# generic_victim.net
KiCad netlist of a schematic drawn in EAGLE
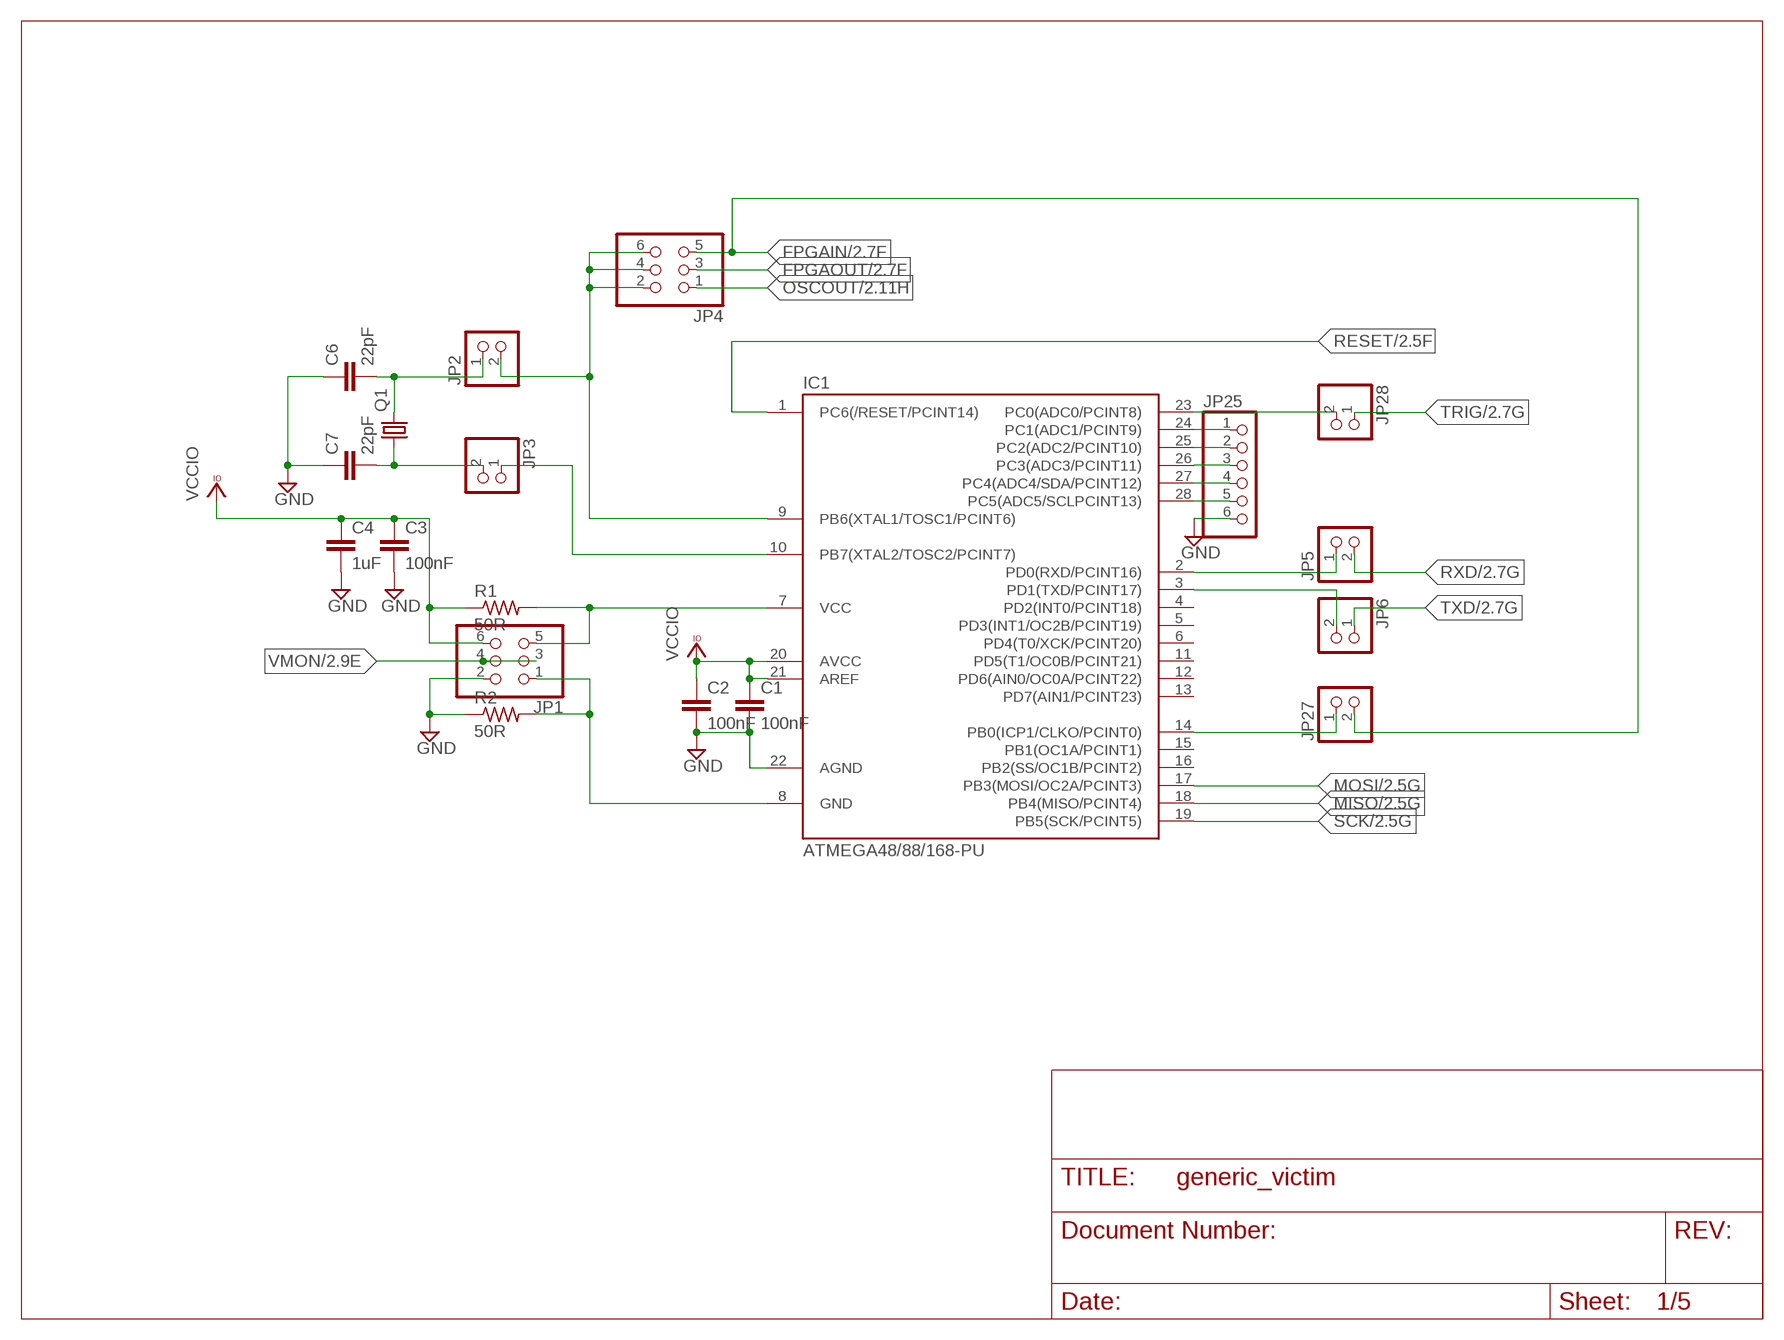
[diagram p0: schematic, sheet 1]
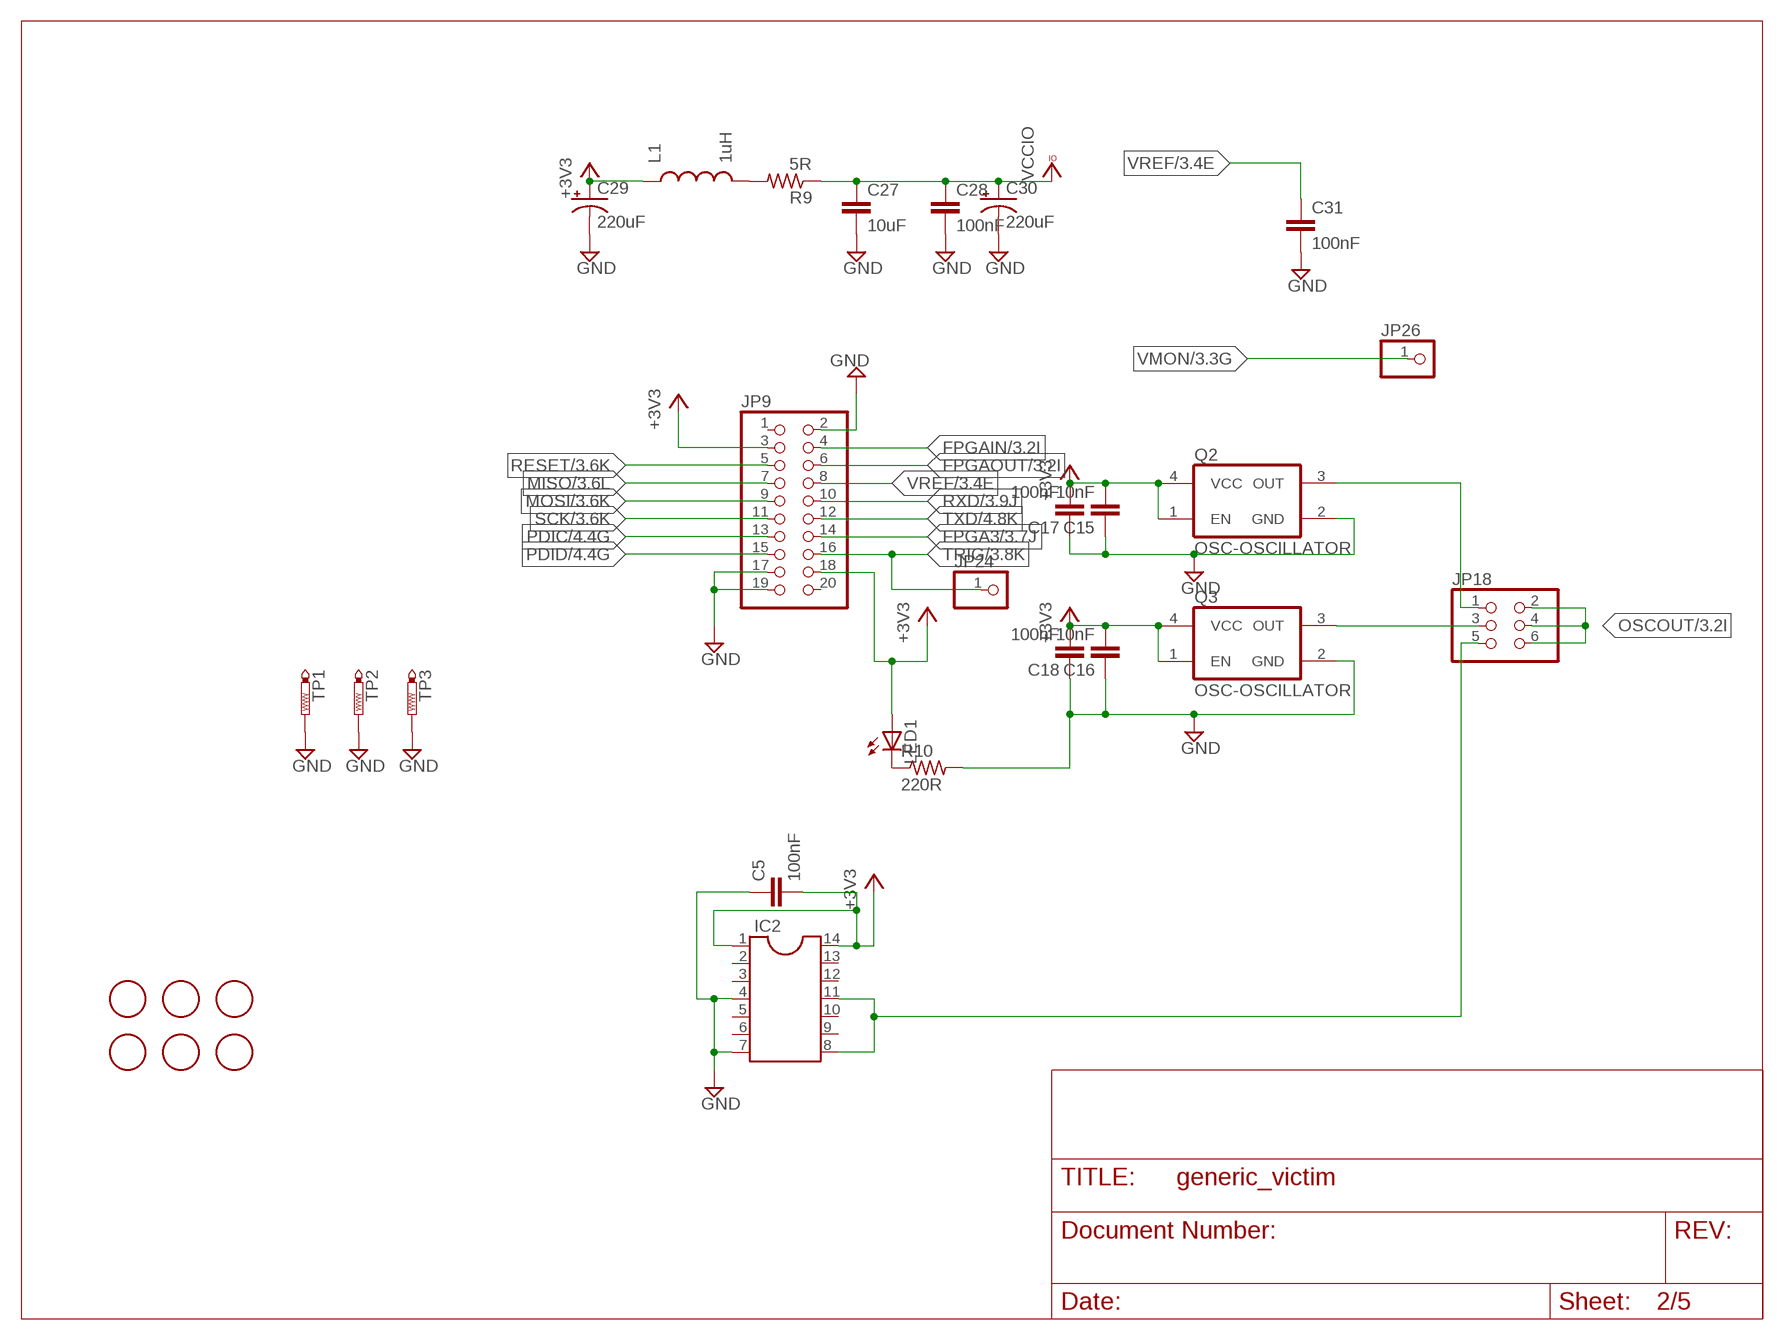
[diagram p1: schematic, sheet 2]
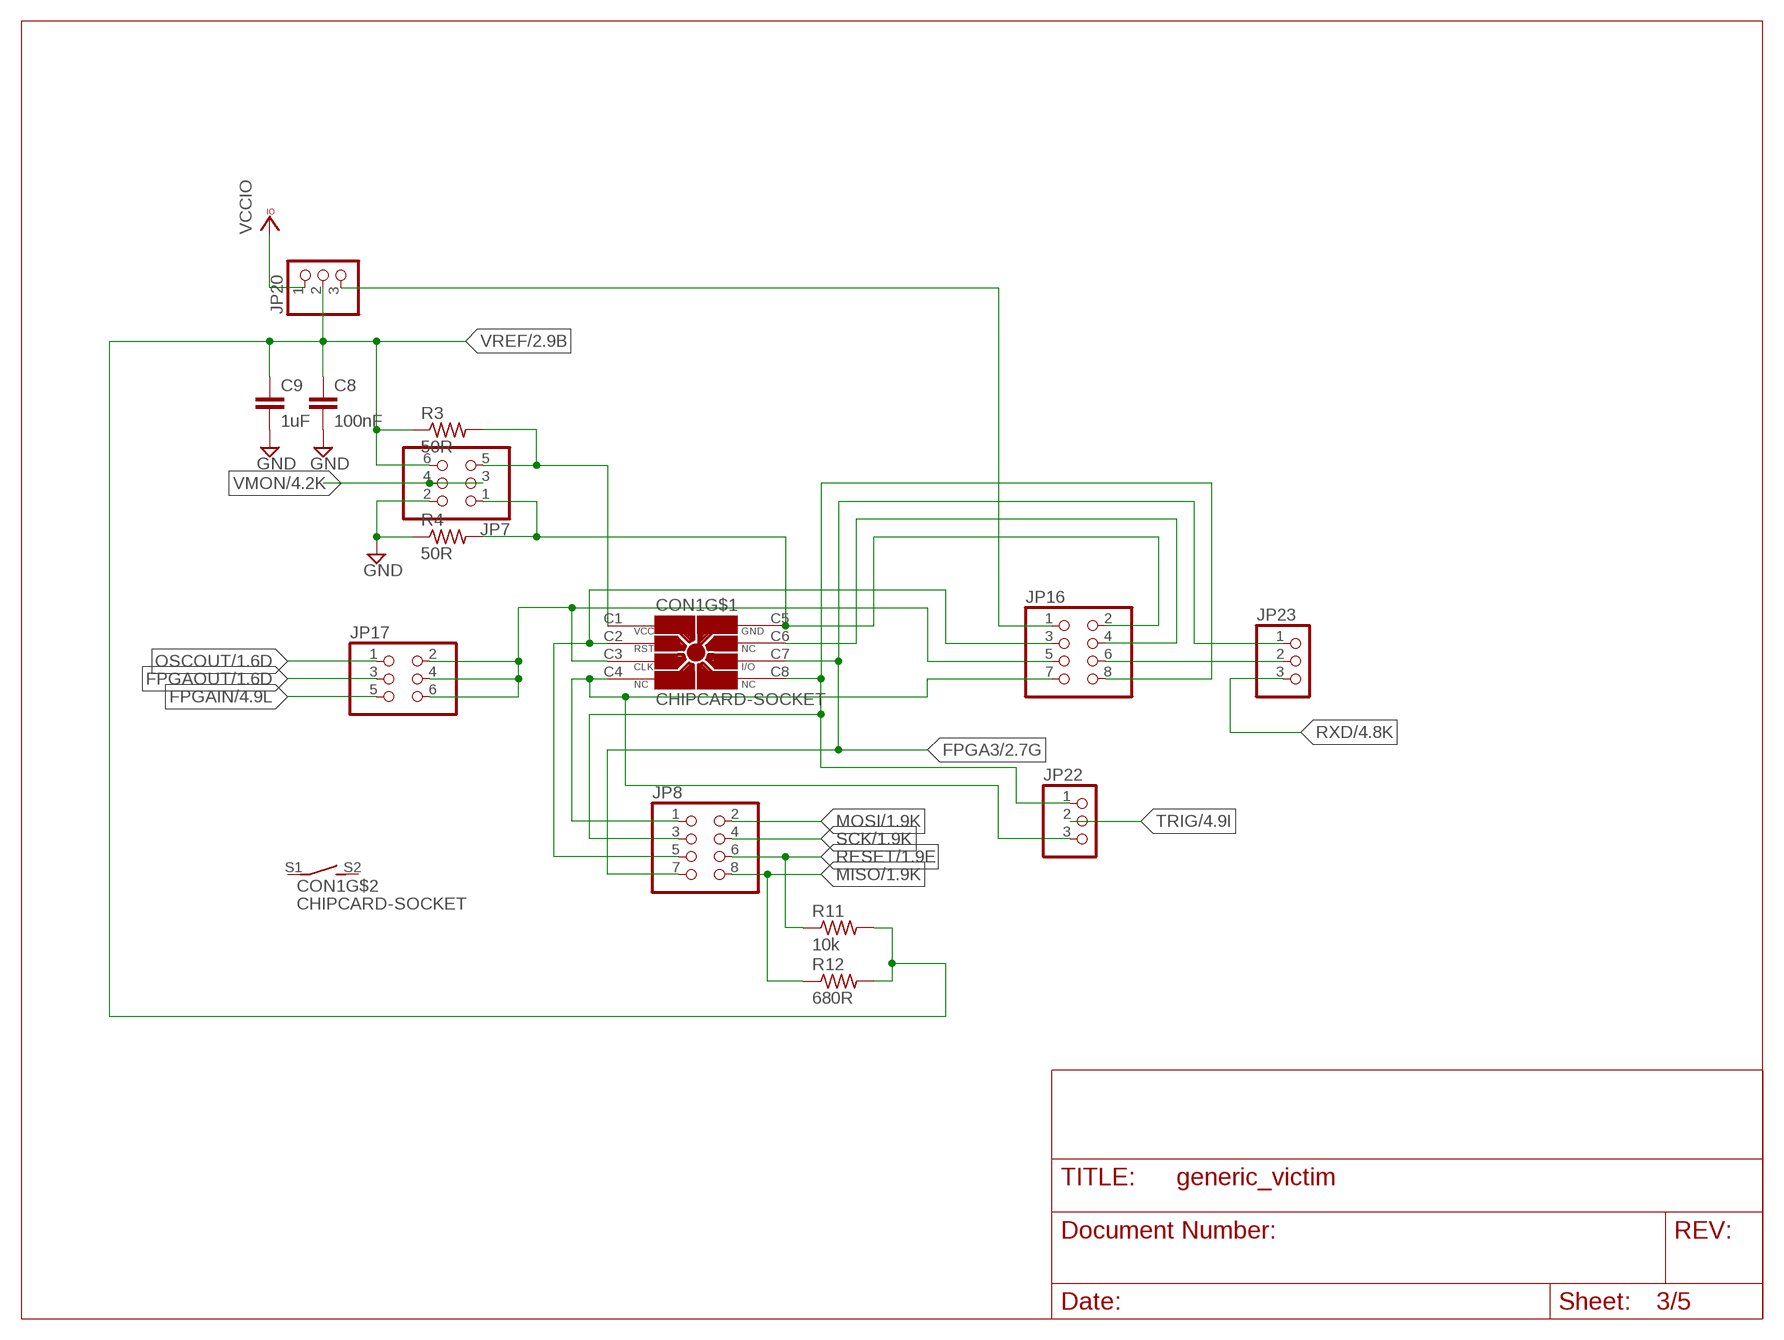
[diagram p2: schematic, sheet 3]
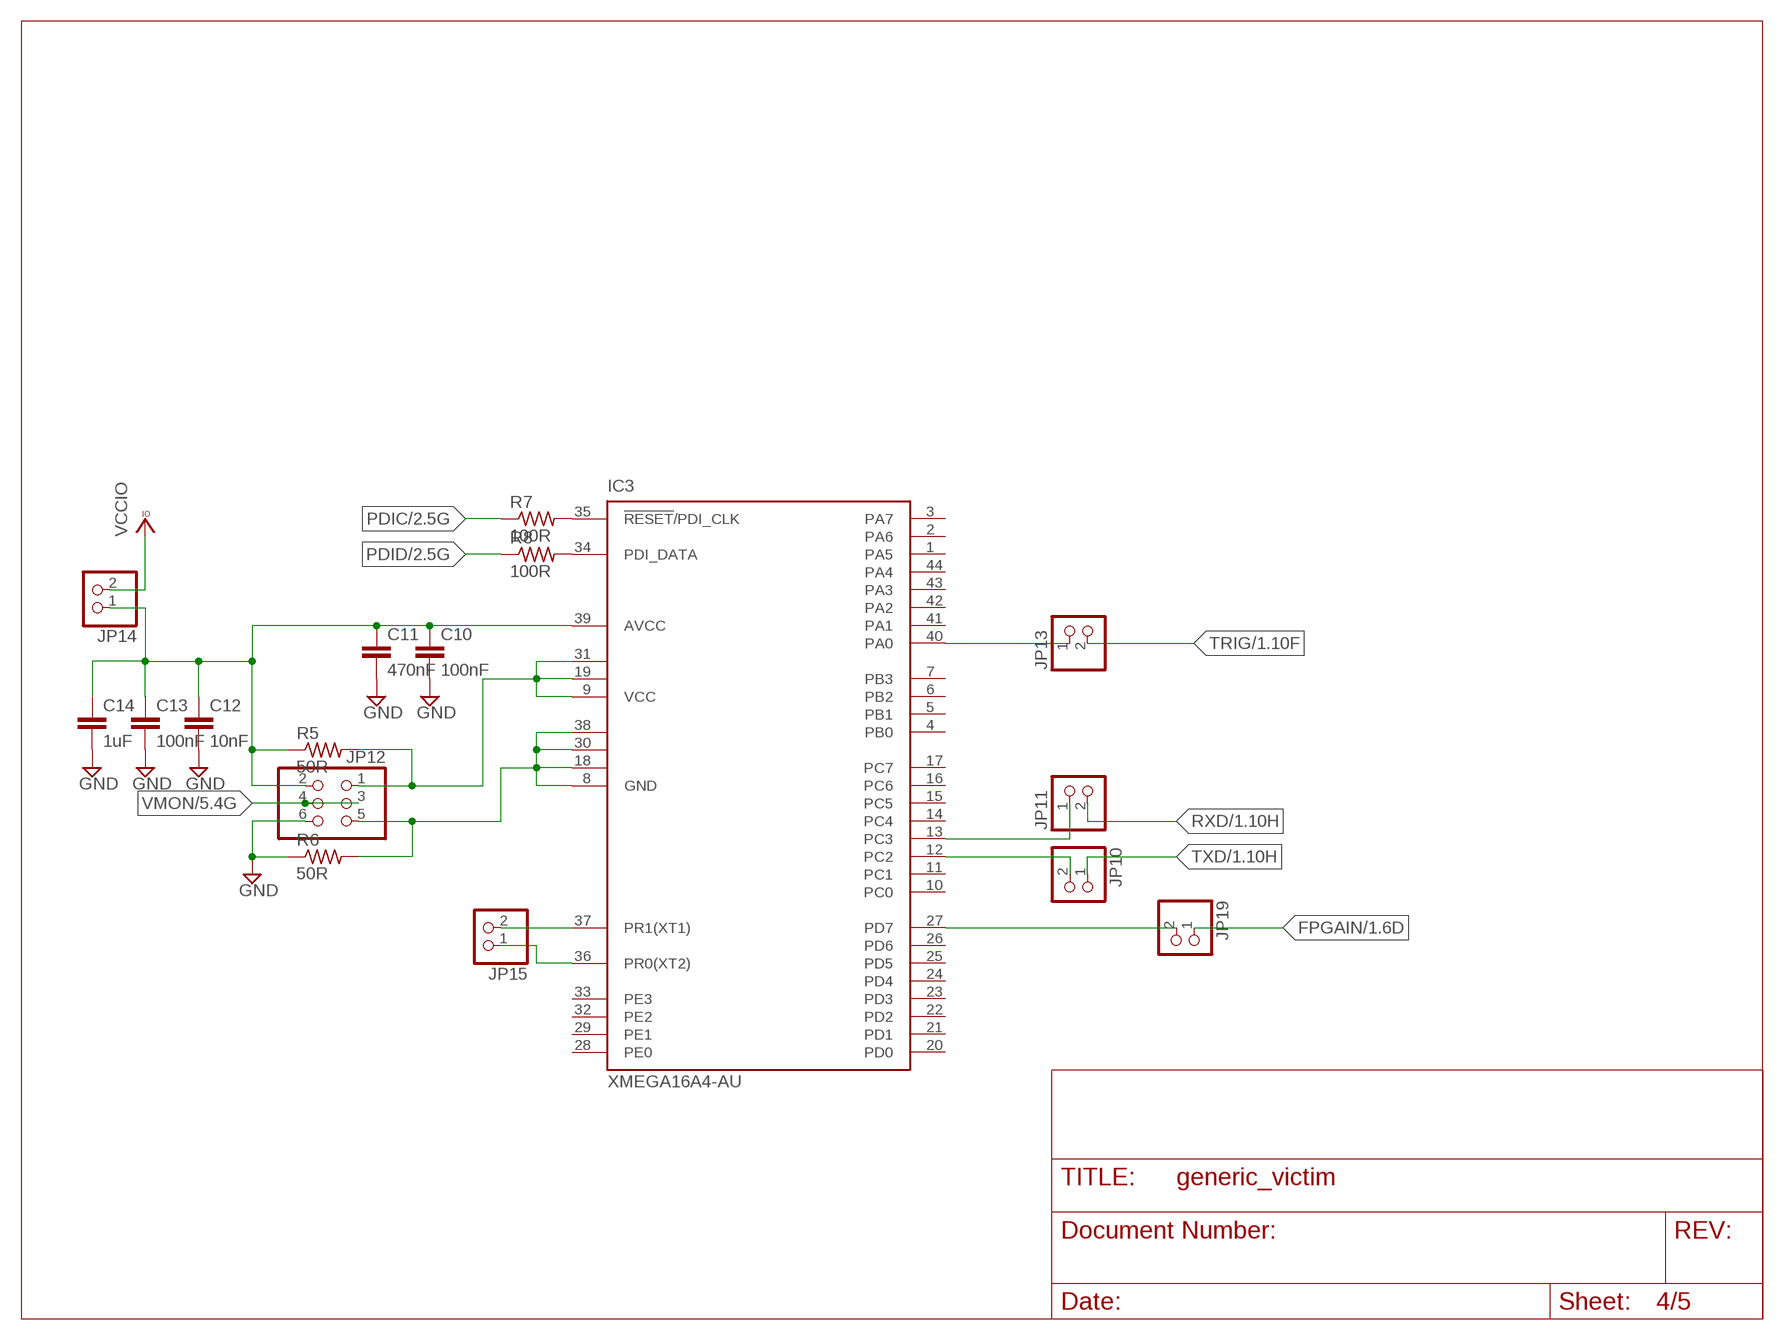
[diagram p3: schematic, sheet 4]
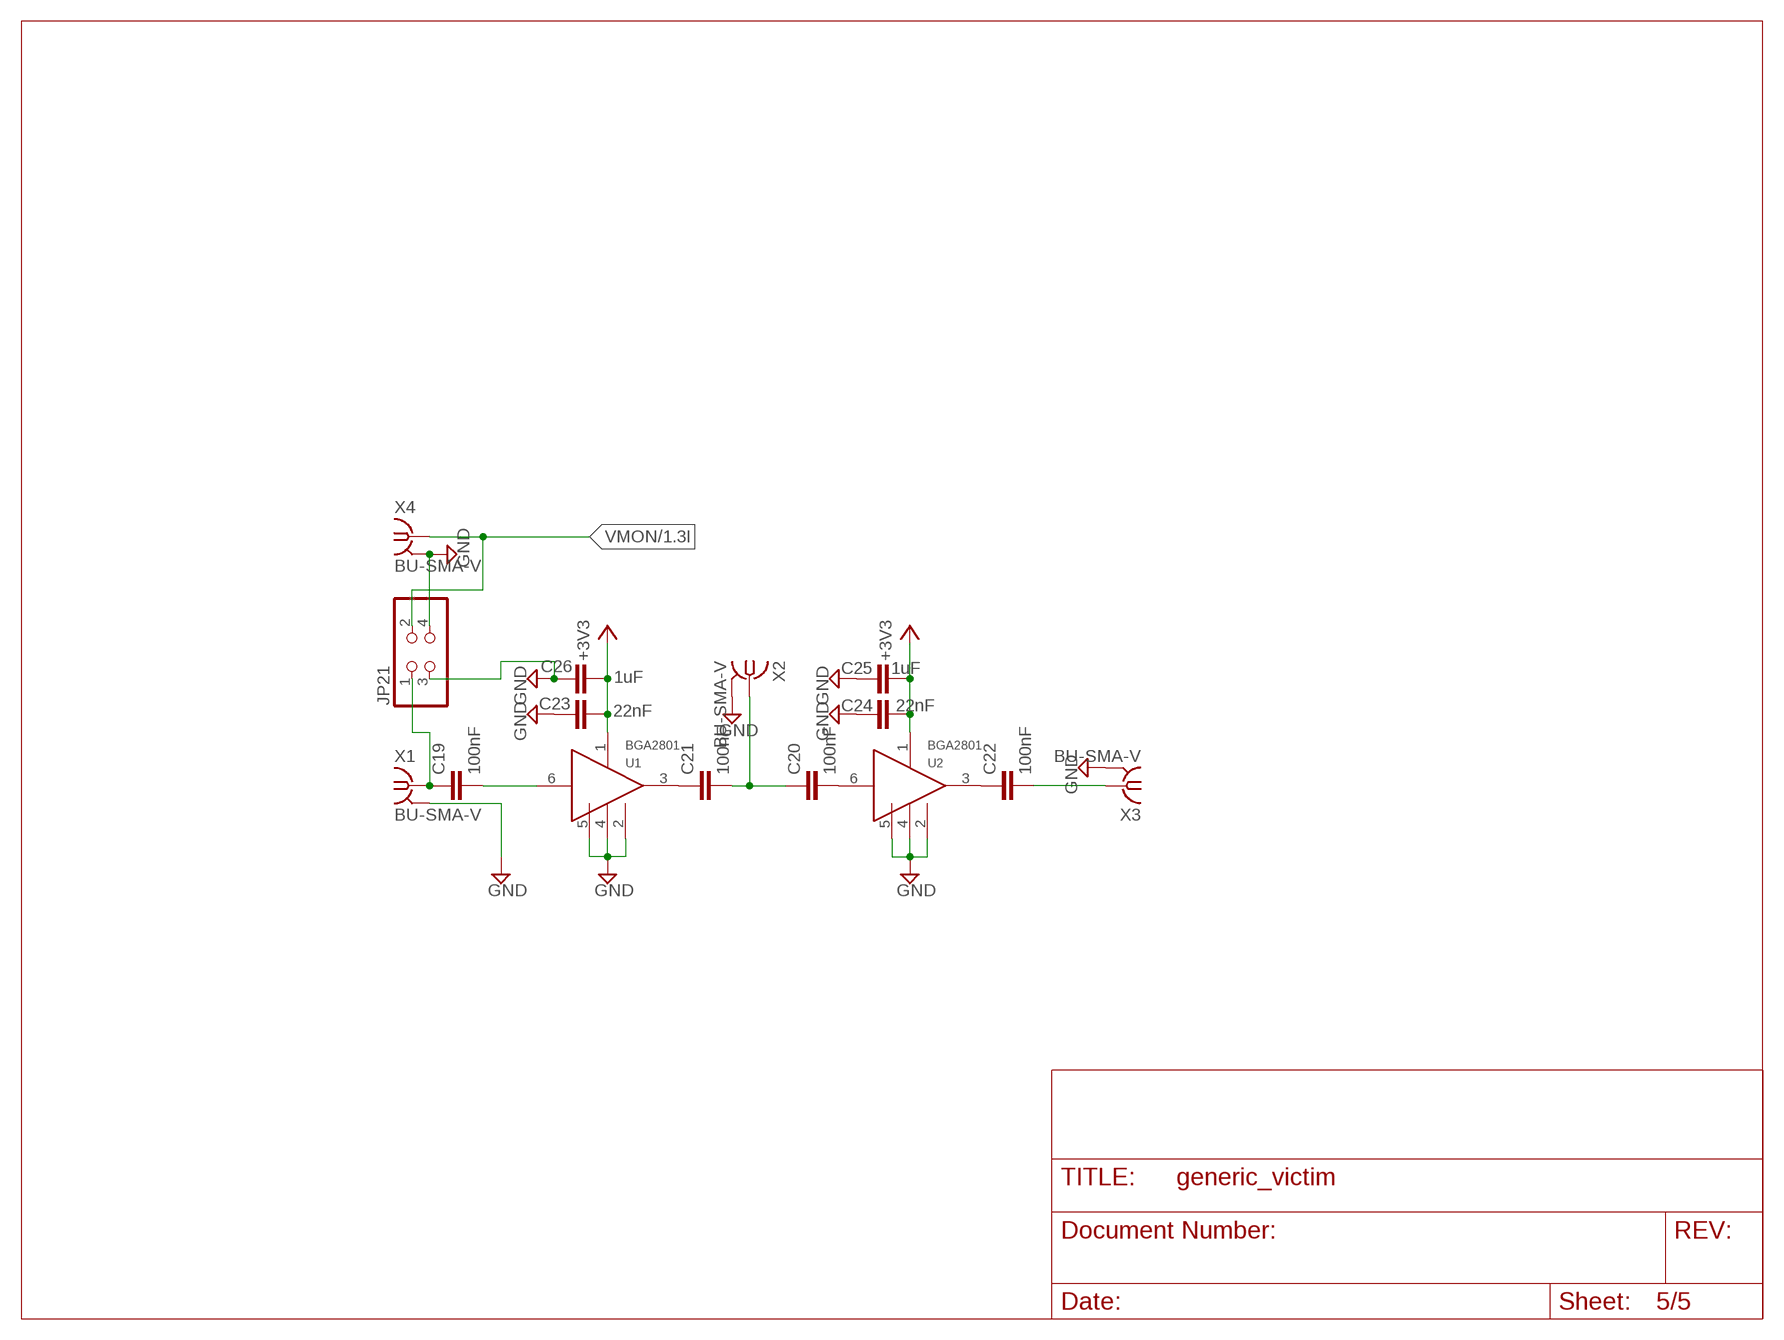
[diagram p4: schematic, sheet 5]

(export (version "E")
  (design (tool "Eeschema 10.0.6"))
  (components
    (comp (ref "C10")
      (value "100nF")
      (footprint "eagle-import:C0805")
      (libsource (lib "eagle-import") (part "resistor_C-EUC0805"))
    )
    (comp (ref "C11")
      (value "470nF")
      (footprint "eagle-import:C0805")
      (libsource (lib "eagle-import") (part "resistor_C-EUC0805"))
    )
    (comp (ref "C12")
      (value "10nF")
      (footprint "eagle-import:C0805")
      (libsource (lib "eagle-import") (part "resistor_C-EUC0805"))
    )
    (comp (ref "C13")
      (value "100nF")
      (footprint "eagle-import:C0805")
      (libsource (lib "eagle-import") (part "resistor_C-EUC0805"))
    )
    (comp (ref "C14")
      (value "1uF")
      (footprint "eagle-import:C0805")
      (libsource (lib "eagle-import") (part "resistor_C-EUC0805"))
    )
    (comp (ref "IC3")
      (value "XMEGA16A4-AU")
      (footprint "eagle-import:TQFP44")
      (libsource (lib "eagle-import") (part "XMEGA16A4A"))
    )
    (comp (ref "JP10")
      (value "PINHD-1X2")
      (footprint "eagle-import:1X02")
      (libsource (lib "eagle-import") (part "PINHD-1X2"))
    )
    (comp (ref "JP11")
      (value "PINHD-1X2")
      (footprint "eagle-import:1X02")
      (libsource (lib "eagle-import") (part "PINHD-1X2"))
    )
    (comp (ref "JP12")
      (value "PINHD-2X3")
      (footprint "eagle-import:2X03")
      (libsource (lib "eagle-import") (part "PINHD-2X3"))
    )
    (comp (ref "JP13")
      (value "PINHD-1X2")
      (footprint "eagle-import:1X02")
      (libsource (lib "eagle-import") (part "PINHD-1X2"))
    )
    (comp (ref "JP14")
      (value "PINHD-1X2")
      (footprint "eagle-import:1X02")
      (libsource (lib "eagle-import") (part "PINHD-1X2"))
    )
    (comp (ref "JP15")
      (value "PINHD-1X2")
      (footprint "eagle-import:1X02")
      (libsource (lib "eagle-import") (part "PINHD-1X2"))
    )
    (comp (ref "JP19")
      (value "PINHD-1X2")
      (footprint "eagle-import:1X02")
      (libsource (lib "eagle-import") (part "PINHD-1X2"))
    )
    (comp (ref "R5")
      (value "50R")
      (footprint "eagle-import:R0805")
      (libsource (lib "eagle-import") (part "resistor_R-US_R0805"))
    )
    (comp (ref "R6")
      (value "50R")
      (footprint "eagle-import:R0805")
      (libsource (lib "eagle-import") (part "resistor_R-US_R0805"))
    )
    (comp (ref "R7")
      (value "100R")
      (footprint "eagle-import:M0805")
      (libsource (lib "eagle-import") (part "resistor_R-US_M0805"))
    )
    (comp (ref "R8")
      (value "100R")
      (footprint "eagle-import:M0805")
      (libsource (lib "eagle-import") (part "resistor_R-US_M0805"))
    )
    (comp (ref "C5")
      (value "100nF")
      (footprint "eagle-import:C0805")
      (libsource (lib "eagle-import") (part "resistor_C-EUC0805"))
    )
    (comp (ref "C15")
      (value "10nF")
      (footprint "eagle-import:C0603")
      (libsource (lib "eagle-import") (part "resistor_C-EUC0603"))
    )
    (comp (ref "C16")
      (value "10nF")
      (footprint "eagle-import:C0603")
      (libsource (lib "eagle-import") (part "resistor_C-EUC0603"))
    )
    (comp (ref "C17")
      (value "100nF")
      (footprint "eagle-import:C0603")
      (libsource (lib "eagle-import") (part "resistor_C-EUC0603"))
    )
    (comp (ref "C18")
      (value "100nF")
      (footprint "eagle-import:C0603")
      (libsource (lib "eagle-import") (part "resistor_C-EUC0603"))
    )
    (comp (ref "C27")
      (value "10uF")
      (footprint "eagle-import:C0805")
      (libsource (lib "eagle-import") (part "C-EUC0805"))
    )
    (comp (ref "C28")
      (value "100nF")
      (footprint "eagle-import:C0805")
      (libsource (lib "eagle-import") (part "C-EUC0805"))
    )
    (comp (ref "C29")
      (value "220uF")
      (footprint "eagle-import:E3,5-8")
      (libsource (lib "eagle-import") (part "CPOL-USE3.5-8"))
    )
    (comp (ref "C30")
      (value "220uF")
      (footprint "eagle-import:E3,5-8")
      (libsource (lib "eagle-import") (part "CPOL-USE3.5-8"))
    )
    (comp (ref "C31")
      (value "100nF")
      (footprint "eagle-import:C0805")
      (libsource (lib "eagle-import") (part "C-EUC0805"))
    )
    (comp (ref "IC2")
      (value "DIL14S")
      (footprint "eagle-import:SOCKET-14")
      (libsource (lib "eagle-import") (part "DIL14S"))
    )
    (comp (ref "JP9")
      (value "PINHD-2X10")
      (footprint "eagle-import:2X10")
      (libsource (lib "eagle-import") (part "PINHD-2X10"))
    )
    (comp (ref "JP18")
      (value "PINHD-2X3")
      (footprint "eagle-import:2X03")
      (libsource (lib "eagle-import") (part "PINHD-2X3"))
    )
    (comp (ref "JP24")
      (value "PINHD-1X1")
      (footprint "eagle-import:1X01")
      (libsource (lib "eagle-import") (part "PINHD-1X1"))
    )
    (comp (ref "JP26")
      (value "PINHD-1X1")
      (footprint "eagle-import:1X01")
      (libsource (lib "eagle-import") (part "PINHD-1X1"))
    )
    (comp (ref "L1")
      (value "1uH")
      (footprint "eagle-import:0805")
      (libsource (lib "eagle-import") (part "INDUCTOR0805"))
    )
    (comp (ref "LED1")
      (value "LED3MM")
      (footprint "eagle-import:LED3MM")
      (libsource (lib "eagle-import") (part "LED3MM"))
    )
    (comp (ref "Q2")
      (value "OSC-OSCILLATOR")
      (footprint "eagle-import:OSCILLATOR_7X5_SMD")
      (libsource (lib "eagle-import") (part "OSC-OSCILLATOR"))
    )
    (comp (ref "Q3")
      (value "OSC-OSCILLATOR")
      (footprint "eagle-import:OSCILLATOR_7X5_SMD")
      (libsource (lib "eagle-import") (part "OSC-OSCILLATOR"))
    )
    (comp (ref "R9")
      (value "5R")
      (footprint "eagle-import:R0805")
      (libsource (lib "eagle-import") (part "R-US_R0805"))
    )
    (comp (ref "R10")
      (value "220R")
      (footprint "eagle-import:R0805")
      (libsource (lib "eagle-import") (part "resistor_R-US_R0805"))
    )
    (comp (ref "TP1")
      (value "PTR1PAD1-13")
      (footprint "eagle-import:P1-13")
      (libsource (lib "eagle-import") (part "PTR1PAD1-13"))
    )
    (comp (ref "TP2")
      (value "PTR1PAD1-13")
      (footprint "eagle-import:P1-13")
      (libsource (lib "eagle-import") (part "PTR1PAD1-13"))
    )
    (comp (ref "TP3")
      (value "PTR1PAD1-13")
      (footprint "eagle-import:P1-13")
      (libsource (lib "eagle-import") (part "PTR1PAD1-13"))
    )
    (comp (ref "U$1")
      (value "FIDUCIAL")
      (footprint "eagle-import:FIDUCIAL_1MM")
      (libsource (lib "eagle-import") (part "FIDUCIAL"))
    )
    (comp (ref "U$2")
      (value "FIDUCIAL")
      (footprint "eagle-import:FIDUCIAL_1MM")
      (libsource (lib "eagle-import") (part "FIDUCIAL"))
    )
    (comp (ref "U$3")
      (value "FIDUCIAL")
      (footprint "eagle-import:FIDUCIAL_1MM")
      (libsource (lib "eagle-import") (part "FIDUCIAL"))
    )
    (comp (ref "U$4")
      (value "FIDUCIAL")
      (footprint "eagle-import:FIDUCIAL_1MM")
      (libsource (lib "eagle-import") (part "FIDUCIAL"))
    )
    (comp (ref "U$5")
      (value "FIDUCIAL")
      (footprint "eagle-import:FIDUCIAL_1MM")
      (libsource (lib "eagle-import") (part "FIDUCIAL"))
    )
    (comp (ref "U$6")
      (value "FIDUCIAL")
      (footprint "eagle-import:FIDUCIAL_1MM")
      (libsource (lib "eagle-import") (part "FIDUCIAL"))
    )
    (comp (ref "C8")
      (value "100nF")
      (footprint "eagle-import:C0805")
      (libsource (lib "eagle-import") (part "resistor_C-EUC0805"))
    )
    (comp (ref "C9")
      (value "1uF")
      (footprint "eagle-import:C0805")
      (libsource (lib "eagle-import") (part "resistor_C-EUC0805"))
    )
    (comp (ref "CON1")
      (value "CHIPCARD-SOCKET")
      (footprint "eagle-import:7334L2622F05LF")
      (libsource (lib "eagle-import") (part "CHIPCARD-SOCKET"))
    )
    (comp (ref "JP7")
      (value "PINHD-2X3")
      (footprint "eagle-import:2X03")
      (libsource (lib "eagle-import") (part "PINHD-2X3"))
    )
    (comp (ref "JP8")
      (value "PINHD-2X4")
      (footprint "eagle-import:2X04")
      (libsource (lib "eagle-import") (part "PINHD-2X4"))
    )
    (comp (ref "JP16")
      (value "PINHD-2X4")
      (footprint "eagle-import:2X04")
      (libsource (lib "eagle-import") (part "PINHD-2X4"))
    )
    (comp (ref "JP17")
      (value "PINHD-2X3")
      (footprint "eagle-import:2X03")
      (libsource (lib "eagle-import") (part "PINHD-2X3"))
    )
    (comp (ref "JP20")
      (value "PINHD-1X3")
      (footprint "eagle-import:1X03")
      (libsource (lib "eagle-import") (part "PINHD-1X3"))
    )
    (comp (ref "JP22")
      (value "PINHD-1X3")
      (footprint "eagle-import:1X03")
      (libsource (lib "eagle-import") (part "PINHD-1X3"))
    )
    (comp (ref "JP23")
      (value "PINHD-1X3")
      (footprint "eagle-import:1X03")
      (libsource (lib "eagle-import") (part "PINHD-1X3"))
    )
    (comp (ref "R3")
      (value "50R")
      (footprint "eagle-import:R0805")
      (libsource (lib "eagle-import") (part "resistor_R-US_R0805"))
    )
    (comp (ref "R4")
      (value "50R")
      (footprint "eagle-import:R0805")
      (libsource (lib "eagle-import") (part "resistor_R-US_R0805"))
    )
    (comp (ref "R11")
      (value "10k")
      (footprint "eagle-import:R0805")
      (libsource (lib "eagle-import") (part "resistor_R-US_R0805"))
    )
    (comp (ref "R12")
      (value "680R")
      (footprint "eagle-import:R0805")
      (libsource (lib "eagle-import") (part "resistor_R-US_R0805"))
    )
    (comp (ref "C19")
      (value "100nF")
      (footprint "eagle-import:C0603")
      (libsource (lib "eagle-import") (part "C-EUC0603"))
    )
    (comp (ref "C20")
      (value "100nF")
      (footprint "eagle-import:C0603")
      (libsource (lib "eagle-import") (part "C-EUC0603"))
    )
    (comp (ref "C21")
      (value "100nF")
      (footprint "eagle-import:C0603")
      (libsource (lib "eagle-import") (part "C-EUC0603"))
    )
    (comp (ref "C22")
      (value "100nF")
      (footprint "eagle-import:C0603")
      (libsource (lib "eagle-import") (part "C-EUC0603"))
    )
    (comp (ref "C23")
      (value "22nF")
      (footprint "eagle-import:C0603")
      (libsource (lib "eagle-import") (part "C-EUC0603"))
    )
    (comp (ref "C24")
      (value "22nF")
      (footprint "eagle-import:C0603")
      (libsource (lib "eagle-import") (part "C-EUC0603"))
    )
    (comp (ref "C25")
      (value "1uF")
      (footprint "eagle-import:C0603")
      (libsource (lib "eagle-import") (part "C-EUC0603"))
    )
    (comp (ref "C26")
      (value "1uF")
      (footprint "eagle-import:C0603")
      (libsource (lib "eagle-import") (part "C-EUC0603"))
    )
    (comp (ref "JP21")
      (value "PINHD-2X2")
      (footprint "eagle-import:2X02")
      (libsource (lib "eagle-import") (part "PINHD-2X2"))
    )
    (comp (ref "U1")
      (value "BGA2801")
      (footprint "eagle-import:SOTT323-6")
      (libsource (lib "eagle-import") (part "BGA2801"))
    )
    (comp (ref "U2")
      (value "BGA2801")
      (footprint "eagle-import:SOTT323-6")
      (libsource (lib "eagle-import") (part "BGA2801"))
    )
    (comp (ref "X1")
      (value "BU-SMA-V")
      (footprint "eagle-import:BU-SMA-V")
      (libsource (lib "eagle-import") (part "BU-SMA-V"))
    )
    (comp (ref "X2")
      (value "BU-SMA-V")
      (footprint "eagle-import:BU-SMA-V")
      (libsource (lib "eagle-import") (part "BU-SMA-V"))
    )
    (comp (ref "X3")
      (value "BU-SMA-V")
      (footprint "eagle-import:BU-SMA-V")
      (libsource (lib "eagle-import") (part "BU-SMA-V"))
    )
    (comp (ref "X4")
      (value "BU-SMA-V")
      (footprint "eagle-import:BU-SMA-V")
      (libsource (lib "eagle-import") (part "BU-SMA-V"))
    )
    (comp (ref "C1")
      (value "100nF")
      (footprint "eagle-import:C0805")
      (libsource (lib "eagle-import") (part "resistor_C-EUC0805"))
    )
    (comp (ref "C2")
      (value "100nF")
      (footprint "eagle-import:C0805")
      (libsource (lib "eagle-import") (part "resistor_C-EUC0805"))
    )
    (comp (ref "C3")
      (value "100nF")
      (footprint "eagle-import:C0805")
      (libsource (lib "eagle-import") (part "resistor_C-EUC0805"))
    )
    (comp (ref "C4")
      (value "1uF")
      (footprint "eagle-import:C0805")
      (libsource (lib "eagle-import") (part "resistor_C-EUC0805"))
    )
    (comp (ref "C6")
      (value "22pF")
      (footprint "eagle-import:C0805")
      (libsource (lib "eagle-import") (part "resistor_C-EUC0805"))
    )
    (comp (ref "C7")
      (value "22pF")
      (footprint "eagle-import:C0805")
      (libsource (lib "eagle-import") (part "resistor_C-EUC0805"))
    )
    (comp (ref "IC1")
      (value "ATMEGA48/88/168-PU")
      (footprint "eagle-import:DIL28-3")
      (libsource (lib "eagle-import") (part "ATMEGA48/88/168-PU"))
    )
    (comp (ref "JP1")
      (value "PINHD-2X3")
      (footprint "eagle-import:2X03")
      (libsource (lib "eagle-import") (part "PINHD-2X3"))
    )
    (comp (ref "JP2")
      (value "PINHD-1X2")
      (footprint "eagle-import:1X02")
      (libsource (lib "eagle-import") (part "PINHD-1X2"))
    )
    (comp (ref "JP3")
      (value "PINHD-1X2")
      (footprint "eagle-import:1X02")
      (libsource (lib "eagle-import") (part "PINHD-1X2"))
    )
    (comp (ref "JP4")
      (value "PINHD-2X3")
      (footprint "eagle-import:2X03")
      (libsource (lib "eagle-import") (part "PINHD-2X3"))
    )
    (comp (ref "JP5")
      (value "PINHD-1X2")
      (footprint "eagle-import:1X02")
      (libsource (lib "eagle-import") (part "PINHD-1X2"))
    )
    (comp (ref "JP6")
      (value "PINHD-1X2")
      (footprint "eagle-import:1X02")
      (libsource (lib "eagle-import") (part "PINHD-1X2"))
    )
    (comp (ref "JP25")
      (value "PINHD-1X6")
      (footprint "eagle-import:1X06")
      (libsource (lib "eagle-import") (part "PINHD-1X6"))
    )
    (comp (ref "JP27")
      (value "PINHD-1X2")
      (footprint "eagle-import:1X02")
      (libsource (lib "eagle-import") (part "PINHD-1X2"))
    )
    (comp (ref "JP28")
      (value "PINHD-1X2")
      (footprint "eagle-import:1X02")
      (libsource (lib "eagle-import") (part "PINHD-1X2"))
    )
    (comp (ref "Q1")
      (value "CRYSTALHC49U70")
      (footprint "eagle-import:HC49U70")
      (libsource (lib "eagle-import") (part "CRYSTALHC49U70"))
    )
    (comp (ref "R1")
      (value "50R")
      (footprint "eagle-import:R0805")
      (libsource (lib "eagle-import") (part "resistor_R-US_R0805"))
    )
    (comp (ref "R2")
      (value "50R")
      (footprint "eagle-import:R0805")
      (libsource (lib "eagle-import") (part "resistor_R-US_R0805"))
    )
  )
  (nets
    (net (code "1") (name "+3V3") (class "Default")
      (node (ref "C15") (pin "2") (pinfunction "2_2") (pintype "passive"))
      (node (ref "C16") (pin "2") (pinfunction "2_2") (pintype "passive"))
      (node (ref "C17") (pin "2") (pinfunction "2_2") (pintype "passive"))
      (node (ref "C18") (pin "2") (pinfunction "2_2") (pintype "passive"))
      (node (ref "C23") (pin "2") (pinfunction "2_2") (pintype "passive"))
      (node (ref "C24") (pin "2") (pinfunction "2_2") (pintype "passive"))
      (node (ref "C25") (pin "2") (pinfunction "2_2") (pintype "passive"))
      (node (ref "C26") (pin "2") (pinfunction "2_2") (pintype "passive"))
      (node (ref "C29") (pin "+") (pinfunction "+_+") (pintype "passive"))
      (node (ref "C5") (pin "2") (pinfunction "2_2") (pintype "passive"))
      (node (ref "IC2") (pin "1") (pinfunction "1_1") (pintype "passive"))
      (node (ref "IC2") (pin "14") (pinfunction "14_14") (pintype "passive"))
      (node (ref "JP9") (pin "18") (pinfunction "18_18") (pintype "passive"))
      (node (ref "JP9") (pin "3") (pinfunction "3_3") (pintype "passive"))
      (node (ref "L1") (pin "1") (pinfunction "1_1") (pintype "passive"))
      (node (ref "LED1") (pin "A") (pinfunction "A_A") (pintype "passive"))
      (node (ref "Q2") (pin "1") (pinfunction "EN_1") (pintype "input"))
      (node (ref "Q2") (pin "4") (pinfunction "VCC_4") (pintype "power_in"))
      (node (ref "Q3") (pin "1") (pinfunction "EN_1") (pintype "input"))
      (node (ref "Q3") (pin "4") (pinfunction "VCC_4") (pintype "power_in"))
      (node (ref "U1") (pin "1") (pinfunction "VCC_1") (pintype "bidirectional"))
      (node (ref "U2") (pin "1") (pinfunction "VCC_1") (pintype "bidirectional"))
    )
    (net (code "2") (name "FPGA3") (class "Default")
      (node (ref "CON1") (pin "C7") (pinfunction "I/O_C7") (pintype "passive"))
      (node (ref "JP23") (pin "1") (pinfunction "1_1") (pintype "passive"))
      (node (ref "JP8") (pin "7") (pinfunction "7_7") (pintype "passive"))
      (node (ref "JP9") (pin "14") (pinfunction "14_14") (pintype "passive"))
    )
    (net (code "3") (name "FPGAIN") (class "Default")
      (node (ref "JP17") (pin "5") (pinfunction "5_5") (pintype "passive"))
      (node (ref "JP19") (pin "1") (pinfunction "1_1") (pintype "passive"))
      (node (ref "JP27") (pin "2") (pinfunction "2_2") (pintype "passive"))
      (node (ref "JP4") (pin "5") (pinfunction "5_5") (pintype "passive"))
      (node (ref "JP9") (pin "4") (pinfunction "4_4") (pintype "passive"))
    )
    (net (code "4") (name "FPGAOUT") (class "Default")
      (node (ref "JP17") (pin "3") (pinfunction "3_3") (pintype "passive"))
      (node (ref "JP4") (pin "3") (pinfunction "3_3") (pintype "passive"))
      (node (ref "JP9") (pin "6") (pinfunction "6_6") (pintype "passive"))
    )
    (net (code "5") (name "GND") (class "Default")
      (node (ref "C1") (pin "2") (pinfunction "2_2") (pintype "passive"))
      (node (ref "C10") (pin "2") (pinfunction "2_2") (pintype "passive"))
      (node (ref "C11") (pin "2") (pinfunction "2_2") (pintype "passive"))
      (node (ref "C12") (pin "2") (pinfunction "2_2") (pintype "passive"))
      (node (ref "C13") (pin "2") (pinfunction "2_2") (pintype "passive"))
      (node (ref "C14") (pin "2") (pinfunction "2_2") (pintype "passive"))
      (node (ref "C15") (pin "1") (pinfunction "1_1") (pintype "passive"))
      (node (ref "C16") (pin "1") (pinfunction "1_1") (pintype "passive"))
      (node (ref "C17") (pin "1") (pinfunction "1_1") (pintype "passive"))
      (node (ref "C18") (pin "1") (pinfunction "1_1") (pintype "passive"))
      (node (ref "C2") (pin "2") (pinfunction "2_2") (pintype "passive"))
      (node (ref "C23") (pin "1") (pinfunction "1_1") (pintype "passive"))
      (node (ref "C24") (pin "1") (pinfunction "1_1") (pintype "passive"))
      (node (ref "C25") (pin "1") (pinfunction "1_1") (pintype "passive"))
      (node (ref "C26") (pin "1") (pinfunction "1_1") (pintype "passive"))
      (node (ref "C27") (pin "2") (pinfunction "2_2") (pintype "passive"))
      (node (ref "C28") (pin "2") (pinfunction "2_2") (pintype "passive"))
      (node (ref "C29") (pin "-") (pinfunction "-_-") (pintype "passive"))
      (node (ref "C3") (pin "2") (pinfunction "2_2") (pintype "passive"))
      (node (ref "C30") (pin "-") (pinfunction "-_-") (pintype "passive"))
      (node (ref "C31") (pin "2") (pinfunction "2_2") (pintype "passive"))
      (node (ref "C4") (pin "2") (pinfunction "2_2") (pintype "passive"))
      (node (ref "C5") (pin "1") (pinfunction "1_1") (pintype "passive"))
      (node (ref "C6") (pin "1") (pinfunction "1_1") (pintype "passive"))
      (node (ref "C7") (pin "1") (pinfunction "1_1") (pintype "passive"))
      (node (ref "C8") (pin "2") (pinfunction "2_2") (pintype "passive"))
      (node (ref "C9") (pin "2") (pinfunction "2_2") (pintype "passive"))
      (node (ref "IC1") (pin "22") (pinfunction "AGND_22") (pintype "power_in"))
      (node (ref "IC2") (pin "4") (pinfunction "4_4") (pintype "passive"))
      (node (ref "IC2") (pin "7") (pinfunction "7_7") (pintype "passive"))
      (node (ref "JP1") (pin "2") (pinfunction "2_2") (pintype "passive"))
      (node (ref "JP12") (pin "6") (pinfunction "6_6") (pintype "passive"))
      (node (ref "JP21") (pin "3") (pinfunction "3_3") (pintype "passive"))
      (node (ref "JP21") (pin "4") (pinfunction "4_4") (pintype "passive"))
      (node (ref "JP25") (pin "6") (pinfunction "6_6") (pintype "passive"))
      (node (ref "JP7") (pin "2") (pinfunction "2_2") (pintype "passive"))
      (node (ref "JP9") (pin "17") (pinfunction "17_17") (pintype "passive"))
      (node (ref "JP9") (pin "19") (pinfunction "19_19") (pintype "passive"))
      (node (ref "JP9") (pin "2") (pinfunction "2_2") (pintype "passive"))
      (node (ref "Q2") (pin "2") (pinfunction "GND_2") (pintype "power_in"))
      (node (ref "Q3") (pin "2") (pinfunction "GND_2") (pintype "power_in"))
      (node (ref "R10") (pin "2") (pinfunction "2_2") (pintype "passive"))
      (node (ref "R2") (pin "1") (pinfunction "1_1") (pintype "passive"))
      (node (ref "R4") (pin "1") (pinfunction "1_1") (pintype "passive"))
      (node (ref "R6") (pin "1") (pinfunction "1_1") (pintype "passive"))
      (node (ref "TP1") (pin "TP") (pinfunction "TP_TP") (pintype "input"))
      (node (ref "TP2") (pin "TP") (pinfunction "TP_TP") (pintype "input"))
      (node (ref "TP3") (pin "TP") (pinfunction "TP_TP") (pintype "input"))
      (node (ref "U1") (pin "2") (pinfunction "GND_2") (pintype "bidirectional"))
      (node (ref "U1") (pin "4") (pinfunction "GND_4") (pintype "bidirectional"))
      (node (ref "U1") (pin "5") (pinfunction "GND_5") (pintype "bidirectional"))
      (node (ref "U2") (pin "2") (pinfunction "GND_2") (pintype "bidirectional"))
      (node (ref "U2") (pin "4") (pinfunction "GND_4") (pintype "bidirectional"))
      (node (ref "U2") (pin "5") (pinfunction "GND_5") (pintype "bidirectional"))
      (node (ref "X1") (pin "2") (pinfunction "2_2") (pintype "passive"))
      (node (ref "X1") (pin "3") (pinfunction "2_3") (pintype "passive"))
      (node (ref "X1") (pin "4") (pinfunction "2_4") (pintype "passive"))
      (node (ref "X1") (pin "5") (pinfunction "2_5") (pintype "passive"))
      (node (ref "X2") (pin "2") (pinfunction "2_2") (pintype "passive"))
      (node (ref "X2") (pin "3") (pinfunction "2_3") (pintype "passive"))
      (node (ref "X2") (pin "4") (pinfunction "2_4") (pintype "passive"))
      (node (ref "X2") (pin "5") (pinfunction "2_5") (pintype "passive"))
      (node (ref "X3") (pin "2") (pinfunction "2_2") (pintype "passive"))
      (node (ref "X3") (pin "3") (pinfunction "2_3") (pintype "passive"))
      (node (ref "X3") (pin "4") (pinfunction "2_4") (pintype "passive"))
      (node (ref "X3") (pin "5") (pinfunction "2_5") (pintype "passive"))
      (node (ref "X4") (pin "2") (pinfunction "2_2") (pintype "passive"))
      (node (ref "X4") (pin "3") (pinfunction "2_3") (pintype "passive"))
      (node (ref "X4") (pin "4") (pinfunction "2_4") (pintype "passive"))
      (node (ref "X4") (pin "5") (pinfunction "2_5") (pintype "passive"))
    )
    (net (code "6") (name "MISO") (class "Default")
      (node (ref "IC1") (pin "18") (pinfunction "PB4(MISO/PCINT4)_18") (pintype "bidirectional"))
      (node (ref "JP8") (pin "8") (pinfunction "8_8") (pintype "passive"))
      (node (ref "JP9") (pin "7") (pinfunction "7_7") (pintype "passive"))
      (node (ref "R12") (pin "1") (pinfunction "1_1") (pintype "passive"))
    )
    (net (code "7") (name "MOSI") (class "Default")
      (node (ref "IC1") (pin "17") (pinfunction "PB3(MOSI/OC2A/PCINT3)_17") (pintype "bidirectional"))
      (node (ref "JP8") (pin "2") (pinfunction "2_2") (pintype "passive"))
      (node (ref "JP9") (pin "9") (pinfunction "9_9") (pintype "passive"))
    )
    (net (code "8") (name "Net-(C6-Pad2)") (class "Default")
      (node (ref "C6") (pin "2") (pinfunction "2_2") (pintype "passive"))
      (node (ref "JP2") (pin "1") (pinfunction "1_1") (pintype "passive"))
      (node (ref "Q1") (pin "2") (pinfunction "2_2") (pintype "passive"))
    )
    (net (code "9") (name "Net-(C7-Pad2)") (class "Default")
      (node (ref "C7") (pin "2") (pinfunction "2_2") (pintype "passive"))
      (node (ref "JP3") (pin "2") (pinfunction "2_2") (pintype "passive"))
      (node (ref "Q1") (pin "1") (pinfunction "1_1") (pintype "passive"))
    )
    (net (code "10") (name "Net-(C19-Pad1)") (class "Default")
      (node (ref "C19") (pin "1") (pinfunction "1_1") (pintype "passive"))
      (node (ref "JP21") (pin "1") (pinfunction "1_1") (pintype "passive"))
      (node (ref "X1") (pin "1") (pinfunction "1_1") (pintype "passive"))
    )
    (net (code "11") (name "Net-(C20-Pad1)") (class "Default")
      (node (ref "C20") (pin "1") (pinfunction "1_1") (pintype "passive"))
      (node (ref "C21") (pin "2") (pinfunction "2_2") (pintype "passive"))
      (node (ref "X2") (pin "1") (pinfunction "1_1") (pintype "passive"))
    )
    (net (code "12") (name "Net-(C22-Pad2)") (class "Default")
      (node (ref "C22") (pin "2") (pinfunction "2_2") (pintype "passive"))
      (node (ref "X3") (pin "1") (pinfunction "1_1") (pintype "passive"))
    )
    (net (code "13") (name "Net-(CON1A-CLK)") (class "Default")
      (node (ref "CON1") (pin "C3") (pinfunction "CLK_C3") (pintype "passive"))
      (node (ref "JP16") (pin "5") (pinfunction "5_5") (pintype "passive"))
      (node (ref "JP17") (pin "2") (pinfunction "2_2") (pintype "passive"))
      (node (ref "JP17") (pin "4") (pinfunction "4_4") (pintype "passive"))
      (node (ref "JP17") (pin "6") (pinfunction "6_6") (pintype "passive"))
    )
    (net (code "14") (name "Net-(CON1A-GND)") (class "Default")
      (node (ref "CON1") (pin "C5") (pinfunction "GND_C5") (pintype "passive"))
      (node (ref "JP16") (pin "2") (pinfunction "2_2") (pintype "passive"))
      (node (ref "JP7") (pin "1") (pinfunction "1_1") (pintype "passive"))
      (node (ref "R4") (pin "2") (pinfunction "2_2") (pintype "passive"))
    )
    (net (code "15") (name "Net-(CON1A-NC-PadC4)") (class "Default")
      (node (ref "CON1") (pin "C4") (pinfunction "NC_C4") (pintype "passive"))
      (node (ref "JP16") (pin "7") (pinfunction "7_7") (pintype "passive"))
      (node (ref "JP22") (pin "3") (pinfunction "3_3") (pintype "passive"))
      (node (ref "JP8") (pin "1") (pinfunction "1_1") (pintype "passive"))
    )
    (net (code "16") (name "Net-(CON1A-NC-PadC6)") (class "Default")
      (node (ref "CON1") (pin "C6") (pinfunction "NC_C6") (pintype "passive"))
      (node (ref "JP16") (pin "4") (pinfunction "4_4") (pintype "passive"))
    )
    (net (code "17") (name "Net-(CON1A-NC-PadC8)") (class "Default")
      (node (ref "CON1") (pin "C8") (pinfunction "NC_C8") (pintype "passive"))
      (node (ref "JP16") (pin "8") (pinfunction "8_8") (pintype "passive"))
      (node (ref "JP22") (pin "1") (pinfunction "1_1") (pintype "passive"))
      (node (ref "JP8") (pin "3") (pinfunction "3_3") (pintype "passive"))
    )
    (net (code "18") (name "Net-(CON1A-RST)") (class "Default")
      (node (ref "CON1") (pin "C2") (pinfunction "RST_C2") (pintype "passive"))
      (node (ref "JP16") (pin "3") (pinfunction "3_3") (pintype "passive"))
      (node (ref "JP8") (pin "5") (pinfunction "5_5") (pintype "passive"))
    )
    (net (code "19") (name "Net-(CON1A-VCC)") (class "Default")
      (node (ref "CON1") (pin "C1") (pinfunction "VCC_C1") (pintype "passive"))
      (node (ref "JP7") (pin "5") (pinfunction "5_5") (pintype "passive"))
      (node (ref "R3") (pin "2") (pinfunction "2_2") (pintype "passive"))
    )
    (net (code "20") (name "Net-(IC1-GND)") (class "Default")
      (node (ref "IC1") (pin "8") (pinfunction "GND_8") (pintype "power_in"))
      (node (ref "JP1") (pin "1") (pinfunction "1_1") (pintype "passive"))
      (node (ref "R2") (pin "2") (pinfunction "2_2") (pintype "passive"))
    )
    (net (code "21") (name "Net-(IC1-PB0(ICP1{slash}CLKO{slash}PCINT0))") (class "Default")
      (node (ref "IC1") (pin "14") (pinfunction "PB0(ICP1/CLKO/PCINT0)_14") (pintype "bidirectional"))
      (node (ref "JP27") (pin "1") (pinfunction "1_1") (pintype "passive"))
    )
    (net (code "22") (name "Net-(IC1-PB6(XTAL1{slash}TOSC1{slash}PCINT6))") (class "Default")
      (node (ref "IC1") (pin "9") (pinfunction "PB6(XTAL1/TOSC1/PCINT6)_9") (pintype "bidirectional"))
      (node (ref "JP2") (pin "2") (pinfunction "2_2") (pintype "passive"))
      (node (ref "JP4") (pin "2") (pinfunction "2_2") (pintype "passive"))
      (node (ref "JP4") (pin "4") (pinfunction "4_4") (pintype "passive"))
      (node (ref "JP4") (pin "6") (pinfunction "6_6") (pintype "passive"))
    )
    (net (code "23") (name "Net-(IC1-PB7(XTAL2{slash}TOSC2{slash}PCINT7))") (class "Default")
      (node (ref "IC1") (pin "10") (pinfunction "PB7(XTAL2/TOSC2/PCINT7)_10") (pintype "bidirectional"))
      (node (ref "JP3") (pin "1") (pinfunction "1_1") (pintype "passive"))
    )
    (net (code "24") (name "Net-(IC1-PC0(ADC0{slash}PCINT8))") (class "Default")
      (node (ref "IC1") (pin "23") (pinfunction "PC0(ADC0/PCINT8)_23") (pintype "bidirectional"))
      (node (ref "JP28") (pin "2") (pinfunction "2_2") (pintype "passive"))
    )
    (net (code "25") (name "Net-(IC1-PC1(ADC1{slash}PCINT9))") (class "Default")
      (node (ref "IC1") (pin "24") (pinfunction "PC1(ADC1/PCINT9)_24") (pintype "bidirectional"))
      (node (ref "JP25") (pin "1") (pinfunction "1_1") (pintype "passive"))
    )
    (net (code "26") (name "Net-(IC1-PC2(ADC2{slash}PCINT10))") (class "Default")
      (node (ref "IC1") (pin "25") (pinfunction "PC2(ADC2/PCINT10)_25") (pintype "bidirectional"))
      (node (ref "JP25") (pin "2") (pinfunction "2_2") (pintype "passive"))
    )
    (net (code "27") (name "Net-(IC1-PC3(ADC3{slash}PCINT11))") (class "Default")
      (node (ref "IC1") (pin "26") (pinfunction "PC3(ADC3/PCINT11)_26") (pintype "bidirectional"))
      (node (ref "JP25") (pin "3") (pinfunction "3_3") (pintype "passive"))
    )
    (net (code "28") (name "Net-(IC1-PC4(ADC4{slash}SDA{slash}PCINT12))") (class "Default")
      (node (ref "IC1") (pin "27") (pinfunction "PC4(ADC4/SDA/PCINT12)_27") (pintype "bidirectional"))
      (node (ref "JP25") (pin "4") (pinfunction "4_4") (pintype "passive"))
    )
    (net (code "29") (name "Net-(IC1-PC5(ADC5{slash}SCLPCINT13))") (class "Default")
      (node (ref "IC1") (pin "28") (pinfunction "PC5(ADC5/SCLPCINT13)_28") (pintype "bidirectional"))
      (node (ref "JP25") (pin "5") (pinfunction "5_5") (pintype "passive"))
    )
    (net (code "30") (name "Net-(IC1-PD0(RXD{slash}PCINT16))") (class "Default")
      (node (ref "IC1") (pin "2") (pinfunction "PD0(RXD/PCINT16)_2") (pintype "bidirectional"))
      (node (ref "JP5") (pin "1") (pinfunction "1_1") (pintype "passive"))
    )
    (net (code "31") (name "Net-(IC1-PD1(TXD{slash}PCINT17))") (class "Default")
      (node (ref "IC1") (pin "3") (pinfunction "PD1(TXD/PCINT17)_3") (pintype "bidirectional"))
      (node (ref "JP6") (pin "2") (pinfunction "2_2") (pintype "passive"))
    )
    (net (code "32") (name "Net-(IC1-VCC)") (class "Default")
      (node (ref "IC1") (pin "7") (pinfunction "VCC_7") (pintype "power_in"))
      (node (ref "JP1") (pin "5") (pinfunction "5_5") (pintype "passive"))
      (node (ref "R1") (pin "2") (pinfunction "2_2") (pintype "passive"))
    )
    (net (code "33") (name "Net-(IC2-Pad11)") (class "Default")
      (node (ref "IC2") (pin "11") (pinfunction "11_11") (pintype "passive"))
      (node (ref "IC2") (pin "8") (pinfunction "8_8") (pintype "passive"))
      (node (ref "JP18") (pin "5") (pinfunction "5_5") (pintype "passive"))
    )
    (net (code "34") (name "Net-(IC3-AVCC)") (class "Default")
      (node (ref "C10") (pin "1") (pinfunction "1_1") (pintype "passive"))
      (node (ref "C11") (pin "1") (pinfunction "1_1") (pintype "passive"))
      (node (ref "C12") (pin "1") (pinfunction "1_1") (pintype "passive"))
      (node (ref "C13") (pin "1") (pinfunction "1_1") (pintype "passive"))
      (node (ref "C14") (pin "1") (pinfunction "1_1") (pintype "passive"))
      (node (ref "IC3") (pin "39") (pinfunction "AVCC_39") (pintype "power_in"))
      (node (ref "JP12") (pin "2") (pinfunction "2_2") (pintype "passive"))
      (node (ref "JP14") (pin "1") (pinfunction "1_1") (pintype "passive"))
      (node (ref "R5") (pin "1") (pinfunction "1_1") (pintype "passive"))
    )
    (net (code "35") (name "Net-(IC3-GND)") (class "Default")
      (node (ref "IC3") (pin "18") (pinfunction "GND1_18") (pintype "power_in"))
      (node (ref "IC3") (pin "30") (pinfunction "GND2_30") (pintype "power_in"))
      (node (ref "IC3") (pin "38") (pinfunction "GND3_38") (pintype "power_in"))
      (node (ref "IC3") (pin "8") (pinfunction "GND_8") (pintype "power_in"))
      (node (ref "JP12") (pin "5") (pinfunction "5_5") (pintype "passive"))
      (node (ref "R6") (pin "2") (pinfunction "2_2") (pintype "passive"))
    )
    (net (code "36") (name "Net-(IC3-PA0)") (class "Default")
      (node (ref "IC3") (pin "40") (pinfunction "PA0_40") (pintype "bidirectional"))
      (node (ref "JP13") (pin "1") (pinfunction "1_1") (pintype "passive"))
    )
    (net (code "37") (name "Net-(IC3-PC2)") (class "Default")
      (node (ref "IC3") (pin "12") (pinfunction "PC2_12") (pintype "bidirectional"))
      (node (ref "JP10") (pin "2") (pinfunction "2_2") (pintype "passive"))
    )
    (net (code "38") (name "Net-(IC3-PC3)") (class "Default")
      (node (ref "IC3") (pin "13") (pinfunction "PC3_13") (pintype "bidirectional"))
      (node (ref "JP11") (pin "1") (pinfunction "1_1") (pintype "passive"))
    )
    (net (code "39") (name "Net-(IC3-PD7)") (class "Default")
      (node (ref "IC3") (pin "27") (pinfunction "PD7_27") (pintype "bidirectional"))
      (node (ref "JP19") (pin "2") (pinfunction "2_2") (pintype "passive"))
    )
    (net (code "40") (name "Net-(IC3-PDI_DATA)") (class "Default")
      (node (ref "IC3") (pin "34") (pinfunction "PDI_DATA_34") (pintype "bidirectional"))
      (node (ref "R8") (pin "2") (pinfunction "2_2") (pintype "passive"))
    )
    (net (code "41") (name "Net-(IC3-PR0(XT2))") (class "Default")
      (node (ref "IC3") (pin "36") (pinfunction "PR0(XT2)_36") (pintype "bidirectional"))
      (node (ref "JP15") (pin "1") (pinfunction "1_1") (pintype "passive"))
    )
    (net (code "42") (name "Net-(IC3-PR1(XT1))") (class "Default")
      (node (ref "IC3") (pin "37") (pinfunction "PR1(XT1)_37") (pintype "bidirectional"))
      (node (ref "JP15") (pin "2") (pinfunction "2_2") (pintype "passive"))
    )
    (net (code "43") (name "Net-(IC3-VCC)") (class "Default")
      (node (ref "IC3") (pin "19") (pinfunction "VCC1_19") (pintype "power_in"))
      (node (ref "IC3") (pin "31") (pinfunction "VCC2_31") (pintype "power_in"))
      (node (ref "IC3") (pin "9") (pinfunction "VCC_9") (pintype "power_in"))
      (node (ref "JP12") (pin "1") (pinfunction "1_1") (pintype "passive"))
      (node (ref "R5") (pin "2") (pinfunction "2_2") (pintype "passive"))
    )
    (net (code "44") (name "Net-(IC3-~{RESET}{slash}PDI_CLK)") (class "Default")
      (node (ref "IC3") (pin "35") (pinfunction "~{RESET}/PDI_CLK_35") (pintype "bidirectional"))
      (node (ref "R7") (pin "2") (pinfunction "2_2") (pintype "passive"))
    )
    (net (code "45") (name "Net-(JP16-Pad1)") (class "Default")
      (node (ref "JP16") (pin "1") (pinfunction "1_1") (pintype "passive"))
      (node (ref "JP20") (pin "3") (pinfunction "3_3") (pintype "passive"))
    )
    (net (code "46") (name "Net-(JP16-Pad6)") (class "Default")
      (node (ref "JP16") (pin "6") (pinfunction "6_6") (pintype "passive"))
      (node (ref "JP23") (pin "2") (pinfunction "2_2") (pintype "passive"))
    )
    (net (code "47") (name "Net-(L1-Pad2)") (class "Default")
      (node (ref "L1") (pin "2") (pinfunction "2_2") (pintype "passive"))
      (node (ref "R9") (pin "2") (pinfunction "2_2") (pintype "passive"))
    )
    (net (code "48") (name "Net-(LED1-C)") (class "Default")
      (node (ref "LED1") (pin "K") (pinfunction "C_K") (pintype "passive"))
      (node (ref "R10") (pin "1") (pinfunction "1_1") (pintype "passive"))
    )
    (net (code "49") (name "Net-(Q2-OUT)") (class "Default")
      (node (ref "JP18") (pin "1") (pinfunction "1_1") (pintype "passive"))
      (node (ref "Q2") (pin "3") (pinfunction "OUT_3") (pintype "output"))
    )
    (net (code "50") (name "Net-(Q3-OUT)") (class "Default")
      (node (ref "JP18") (pin "3") (pinfunction "3_3") (pintype "passive"))
      (node (ref "Q3") (pin "3") (pinfunction "OUT_3") (pintype "output"))
    )
    (net (code "51") (name "Net-(U1-IN)") (class "Default")
      (node (ref "C19") (pin "2") (pinfunction "2_2") (pintype "passive"))
      (node (ref "U1") (pin "6") (pinfunction "IN_6") (pintype "bidirectional"))
    )
    (net (code "52") (name "Net-(U1-OUT)") (class "Default")
      (node (ref "C21") (pin "1") (pinfunction "1_1") (pintype "passive"))
      (node (ref "U1") (pin "3") (pinfunction "OUT_3") (pintype "bidirectional"))
    )
    (net (code "53") (name "Net-(U2-IN)") (class "Default")
      (node (ref "C20") (pin "2") (pinfunction "2_2") (pintype "passive"))
      (node (ref "U2") (pin "6") (pinfunction "IN_6") (pintype "bidirectional"))
    )
    (net (code "54") (name "Net-(U2-OUT)") (class "Default")
      (node (ref "C22") (pin "1") (pinfunction "1_1") (pintype "passive"))
      (node (ref "U2") (pin "3") (pinfunction "OUT_3") (pintype "bidirectional"))
    )
    (net (code "55") (name "OSCOUT") (class "Default")
      (node (ref "JP17") (pin "1") (pinfunction "1_1") (pintype "passive"))
      (node (ref "JP18") (pin "2") (pinfunction "2_2") (pintype "passive"))
      (node (ref "JP18") (pin "4") (pinfunction "4_4") (pintype "passive"))
      (node (ref "JP18") (pin "6") (pinfunction "6_6") (pintype "passive"))
      (node (ref "JP4") (pin "1") (pinfunction "1_1") (pintype "passive"))
    )
    (net (code "56") (name "PDIC") (class "Default")
      (node (ref "JP9") (pin "13") (pinfunction "13_13") (pintype "passive"))
      (node (ref "R7") (pin "1") (pinfunction "1_1") (pintype "passive"))
    )
    (net (code "57") (name "PDID") (class "Default")
      (node (ref "JP9") (pin "15") (pinfunction "15_15") (pintype "passive"))
      (node (ref "R8") (pin "1") (pinfunction "1_1") (pintype "passive"))
    )
    (net (code "58") (name "RESET") (class "Default")
      (node (ref "IC1") (pin "1") (pinfunction "PC6(/RESET/PCINT14)_1") (pintype "bidirectional"))
      (node (ref "JP8") (pin "6") (pinfunction "6_6") (pintype "passive"))
      (node (ref "JP9") (pin "5") (pinfunction "5_5") (pintype "passive"))
      (node (ref "R11") (pin "1") (pinfunction "1_1") (pintype "passive"))
    )
    (net (code "59") (name "RXD") (class "Default")
      (node (ref "JP11") (pin "2") (pinfunction "2_2") (pintype "passive"))
      (node (ref "JP23") (pin "3") (pinfunction "3_3") (pintype "passive"))
      (node (ref "JP5") (pin "2") (pinfunction "2_2") (pintype "passive"))
      (node (ref "JP9") (pin "10") (pinfunction "10_10") (pintype "passive"))
    )
    (net (code "60") (name "SCK") (class "Default")
      (node (ref "IC1") (pin "19") (pinfunction "PB5(SCK/PCINT5)_19") (pintype "bidirectional"))
      (node (ref "JP8") (pin "4") (pinfunction "4_4") (pintype "passive"))
      (node (ref "JP9") (pin "11") (pinfunction "11_11") (pintype "passive"))
    )
    (net (code "61") (name "TRIG") (class "Default")
      (node (ref "JP13") (pin "2") (pinfunction "2_2") (pintype "passive"))
      (node (ref "JP22") (pin "2") (pinfunction "2_2") (pintype "passive"))
      (node (ref "JP24") (pin "1") (pinfunction "1_1") (pintype "passive"))
      (node (ref "JP28") (pin "1") (pinfunction "1_1") (pintype "passive"))
      (node (ref "JP9") (pin "16") (pinfunction "16_16") (pintype "passive"))
    )
    (net (code "62") (name "TXD") (class "Default")
      (node (ref "JP10") (pin "1") (pinfunction "1_1") (pintype "passive"))
      (node (ref "JP6") (pin "1") (pinfunction "1_1") (pintype "passive"))
      (node (ref "JP9") (pin "12") (pinfunction "12_12") (pintype "passive"))
    )
    (net (code "63") (name "VCCIO") (class "Default")
      (node (ref "C1") (pin "1") (pinfunction "1_1") (pintype "passive"))
      (node (ref "C2") (pin "1") (pinfunction "1_1") (pintype "passive"))
      (node (ref "C27") (pin "1") (pinfunction "1_1") (pintype "passive"))
      (node (ref "C28") (pin "1") (pinfunction "1_1") (pintype "passive"))
      (node (ref "C3") (pin "1") (pinfunction "1_1") (pintype "passive"))
      (node (ref "C30") (pin "+") (pinfunction "+_+") (pintype "passive"))
      (node (ref "C4") (pin "1") (pinfunction "1_1") (pintype "passive"))
      (node (ref "IC1") (pin "20") (pinfunction "AVCC_20") (pintype "passive"))
      (node (ref "IC1") (pin "21") (pinfunction "AREF_21") (pintype "passive"))
      (node (ref "JP1") (pin "6") (pinfunction "6_6") (pintype "passive"))
      (node (ref "JP14") (pin "2") (pinfunction "2_2") (pintype "passive"))
      (node (ref "JP20") (pin "1") (pinfunction "1_1") (pintype "passive"))
      (node (ref "R1") (pin "1") (pinfunction "1_1") (pintype "passive"))
      (node (ref "R9") (pin "1") (pinfunction "1_1") (pintype "passive"))
    )
    (net (code "64") (name "VMON") (class "Default")
      (node (ref "JP1") (pin "3") (pinfunction "3_3") (pintype "passive"))
      (node (ref "JP1") (pin "4") (pinfunction "4_4") (pintype "passive"))
      (node (ref "JP12") (pin "3") (pinfunction "3_3") (pintype "passive"))
      (node (ref "JP12") (pin "4") (pinfunction "4_4") (pintype "passive"))
      (node (ref "JP21") (pin "2") (pinfunction "2_2") (pintype "passive"))
      (node (ref "JP26") (pin "1") (pinfunction "1_1") (pintype "passive"))
      (node (ref "JP7") (pin "3") (pinfunction "3_3") (pintype "passive"))
      (node (ref "JP7") (pin "4") (pinfunction "4_4") (pintype "passive"))
      (node (ref "X4") (pin "1") (pinfunction "1_1") (pintype "passive"))
    )
    (net (code "65") (name "VREF") (class "Default")
      (node (ref "C31") (pin "1") (pinfunction "1_1") (pintype "passive"))
      (node (ref "C8") (pin "1") (pinfunction "1_1") (pintype "passive"))
      (node (ref "C9") (pin "1") (pinfunction "1_1") (pintype "passive"))
      (node (ref "JP20") (pin "2") (pinfunction "2_2") (pintype "passive"))
      (node (ref "JP7") (pin "6") (pinfunction "6_6") (pintype "passive"))
      (node (ref "JP9") (pin "8") (pinfunction "8_8") (pintype "passive"))
      (node (ref "R11") (pin "2") (pinfunction "2_2") (pintype "passive"))
      (node (ref "R12") (pin "2") (pinfunction "2_2") (pintype "passive"))
      (node (ref "R3") (pin "1") (pinfunction "1_1") (pintype "passive"))
    )
    (net (code "66") (name "unconnected-(CON1B-1-PadS1)") (class "Default")
      (node (ref "CON1") (pin "S1") (pinfunction "1_S1") (pintype "passive"))
    )
    (net (code "67") (name "unconnected-(CON1B-2-PadS2)") (class "Default")
      (node (ref "CON1") (pin "S2") (pinfunction "2_S2") (pintype "passive"))
    )
    (net (code "68") (name "unconnected-(IC1-PB1(OC1A{slash}PCINT1)-Pad15)") (class "Default")
      (node (ref "IC1") (pin "15") (pinfunction "PB1(OC1A/PCINT1)_15") (pintype "bidirectional"))
    )
    (net (code "69") (name "unconnected-(IC1-PB2(SS{slash}OC1B{slash}PCINT2)-Pad16)") (class "Default")
      (node (ref "IC1") (pin "16") (pinfunction "PB2(SS/OC1B/PCINT2)_16") (pintype "bidirectional"))
    )
    (net (code "70") (name "unconnected-(IC1-PD2(INT0{slash}PCINT18)-Pad4)") (class "Default")
      (node (ref "IC1") (pin "4") (pinfunction "PD2(INT0/PCINT18)_4") (pintype "bidirectional"))
    )
    (net (code "71") (name "unconnected-(IC1-PD3(INT1{slash}OC2B{slash}PCINT19)-Pad5)") (class "Default")
      (node (ref "IC1") (pin "5") (pinfunction "PD3(INT1/OC2B/PCINT19)_5") (pintype "bidirectional"))
    )
    (net (code "72") (name "unconnected-(IC1-PD4(T0{slash}XCK{slash}PCINT20)-Pad6)") (class "Default")
      (node (ref "IC1") (pin "6") (pinfunction "PD4(T0/XCK/PCINT20)_6") (pintype "bidirectional"))
    )
    (net (code "73") (name "unconnected-(IC1-PD5(T1{slash}OC0B{slash}PCINT21)-Pad11)") (class "Default")
      (node (ref "IC1") (pin "11") (pinfunction "PD5(T1/OC0B/PCINT21)_11") (pintype "bidirectional"))
    )
    (net (code "74") (name "unconnected-(IC1-PD6(AIN0{slash}OC0A{slash}PCINT22)-Pad12)") (class "Default")
      (node (ref "IC1") (pin "12") (pinfunction "PD6(AIN0/OC0A/PCINT22)_12") (pintype "bidirectional"))
    )
    (net (code "75") (name "unconnected-(IC1-PD7(AIN1{slash}PCINT23)-Pad13)") (class "Default")
      (node (ref "IC1") (pin "13") (pinfunction "PD7(AIN1/PCINT23)_13") (pintype "bidirectional"))
    )
    (net (code "76") (name "unconnected-(IC2-Pad2)") (class "Default")
      (node (ref "IC2") (pin "2") (pinfunction "2_2") (pintype "passive"))
    )
    (net (code "77") (name "unconnected-(IC2-Pad3)") (class "Default")
      (node (ref "IC2") (pin "3") (pinfunction "3_3") (pintype "passive"))
    )
    (net (code "78") (name "unconnected-(IC2-Pad5)") (class "Default")
      (node (ref "IC2") (pin "5") (pinfunction "5_5") (pintype "passive"))
    )
    (net (code "79") (name "unconnected-(IC2-Pad6)") (class "Default")
      (node (ref "IC2") (pin "6") (pinfunction "6_6") (pintype "passive"))
    )
    (net (code "80") (name "unconnected-(IC2-Pad9)") (class "Default")
      (node (ref "IC2") (pin "9") (pinfunction "9_9") (pintype "passive"))
    )
    (net (code "81") (name "unconnected-(IC2-Pad10)") (class "Default")
      (node (ref "IC2") (pin "10") (pinfunction "10_10") (pintype "passive"))
    )
    (net (code "82") (name "unconnected-(IC2-Pad12)") (class "Default")
      (node (ref "IC2") (pin "12") (pinfunction "12_12") (pintype "passive"))
    )
    (net (code "83") (name "unconnected-(IC2-Pad13)") (class "Default")
      (node (ref "IC2") (pin "13") (pinfunction "13_13") (pintype "passive"))
    )
    (net (code "84") (name "unconnected-(IC3-PA1-Pad41)") (class "Default")
      (node (ref "IC3") (pin "41") (pinfunction "PA1_41") (pintype "bidirectional"))
    )
    (net (code "85") (name "unconnected-(IC3-PA2-Pad42)") (class "Default")
      (node (ref "IC3") (pin "42") (pinfunction "PA2_42") (pintype "bidirectional"))
    )
    (net (code "86") (name "unconnected-(IC3-PA3-Pad43)") (class "Default")
      (node (ref "IC3") (pin "43") (pinfunction "PA3_43") (pintype "bidirectional"))
    )
    (net (code "87") (name "unconnected-(IC3-PA4-Pad44)") (class "Default")
      (node (ref "IC3") (pin "44") (pinfunction "PA4_44") (pintype "bidirectional"))
    )
    (net (code "88") (name "unconnected-(IC3-PA5-Pad1)") (class "Default")
      (node (ref "IC3") (pin "1") (pinfunction "PA5_1") (pintype "bidirectional"))
    )
    (net (code "89") (name "unconnected-(IC3-PA6-Pad2)") (class "Default")
      (node (ref "IC3") (pin "2") (pinfunction "PA6_2") (pintype "bidirectional"))
    )
    (net (code "90") (name "unconnected-(IC3-PA7-Pad3)") (class "Default")
      (node (ref "IC3") (pin "3") (pinfunction "PA7_3") (pintype "bidirectional"))
    )
    (net (code "91") (name "unconnected-(IC3-PB0-Pad4)") (class "Default")
      (node (ref "IC3") (pin "4") (pinfunction "PB0_4") (pintype "bidirectional"))
    )
    (net (code "92") (name "unconnected-(IC3-PB1-Pad5)") (class "Default")
      (node (ref "IC3") (pin "5") (pinfunction "PB1_5") (pintype "bidirectional"))
    )
    (net (code "93") (name "unconnected-(IC3-PB2-Pad6)") (class "Default")
      (node (ref "IC3") (pin "6") (pinfunction "PB2_6") (pintype "bidirectional"))
    )
    (net (code "94") (name "unconnected-(IC3-PB3-Pad7)") (class "Default")
      (node (ref "IC3") (pin "7") (pinfunction "PB3_7") (pintype "bidirectional"))
    )
    (net (code "95") (name "unconnected-(IC3-PC0-Pad10)") (class "Default")
      (node (ref "IC3") (pin "10") (pinfunction "PC0_10") (pintype "bidirectional"))
    )
    (net (code "96") (name "unconnected-(IC3-PC1-Pad11)") (class "Default")
      (node (ref "IC3") (pin "11") (pinfunction "PC1_11") (pintype "bidirectional"))
    )
    (net (code "97") (name "unconnected-(IC3-PC4-Pad14)") (class "Default")
      (node (ref "IC3") (pin "14") (pinfunction "PC4_14") (pintype "bidirectional"))
    )
    (net (code "98") (name "unconnected-(IC3-PC5-Pad15)") (class "Default")
      (node (ref "IC3") (pin "15") (pinfunction "PC5_15") (pintype "bidirectional"))
    )
    (net (code "99") (name "unconnected-(IC3-PC6-Pad16)") (class "Default")
      (node (ref "IC3") (pin "16") (pinfunction "PC6_16") (pintype "bidirectional"))
    )
    (net (code "100") (name "unconnected-(IC3-PC7-Pad17)") (class "Default")
      (node (ref "IC3") (pin "17") (pinfunction "PC7_17") (pintype "bidirectional"))
    )
    (net (code "101") (name "unconnected-(IC3-PD0-Pad20)") (class "Default")
      (node (ref "IC3") (pin "20") (pinfunction "PD0_20") (pintype "bidirectional"))
    )
    (net (code "102") (name "unconnected-(IC3-PD1-Pad21)") (class "Default")
      (node (ref "IC3") (pin "21") (pinfunction "PD1_21") (pintype "bidirectional"))
    )
    (net (code "103") (name "unconnected-(IC3-PD2-Pad22)") (class "Default")
      (node (ref "IC3") (pin "22") (pinfunction "PD2_22") (pintype "bidirectional"))
    )
    (net (code "104") (name "unconnected-(IC3-PD3-Pad23)") (class "Default")
      (node (ref "IC3") (pin "23") (pinfunction "PD3_23") (pintype "bidirectional"))
    )
    (net (code "105") (name "unconnected-(IC3-PD4-Pad24)") (class "Default")
      (node (ref "IC3") (pin "24") (pinfunction "PD4_24") (pintype "bidirectional"))
    )
    (net (code "106") (name "unconnected-(IC3-PD5-Pad25)") (class "Default")
      (node (ref "IC3") (pin "25") (pinfunction "PD5_25") (pintype "bidirectional"))
    )
    (net (code "107") (name "unconnected-(IC3-PD6-Pad26)") (class "Default")
      (node (ref "IC3") (pin "26") (pinfunction "PD6_26") (pintype "bidirectional"))
    )
    (net (code "108") (name "unconnected-(IC3-PE0-Pad28)") (class "Default")
      (node (ref "IC3") (pin "28") (pinfunction "PE0_28") (pintype "bidirectional"))
    )
    (net (code "109") (name "unconnected-(IC3-PE1-Pad29)") (class "Default")
      (node (ref "IC3") (pin "29") (pinfunction "PE1_29") (pintype "bidirectional"))
    )
    (net (code "110") (name "unconnected-(IC3-PE2-Pad32)") (class "Default")
      (node (ref "IC3") (pin "32") (pinfunction "PE2_32") (pintype "bidirectional"))
    )
    (net (code "111") (name "unconnected-(IC3-PE3-Pad33)") (class "Default")
      (node (ref "IC3") (pin "33") (pinfunction "PE3_33") (pintype "bidirectional"))
    )
    (net (code "112") (name "unconnected-(JP9-Pad1)") (class "Default")
      (node (ref "JP9") (pin "1") (pinfunction "1_1") (pintype "passive"))
    )
    (net (code "113") (name "unconnected-(JP9-Pad20)") (class "Default")
      (node (ref "JP9") (pin "20") (pinfunction "20_20") (pintype "passive"))
    )
  )
)
